# connector_v3.net
KiCad netlist of a schematic drawn in EAGLE
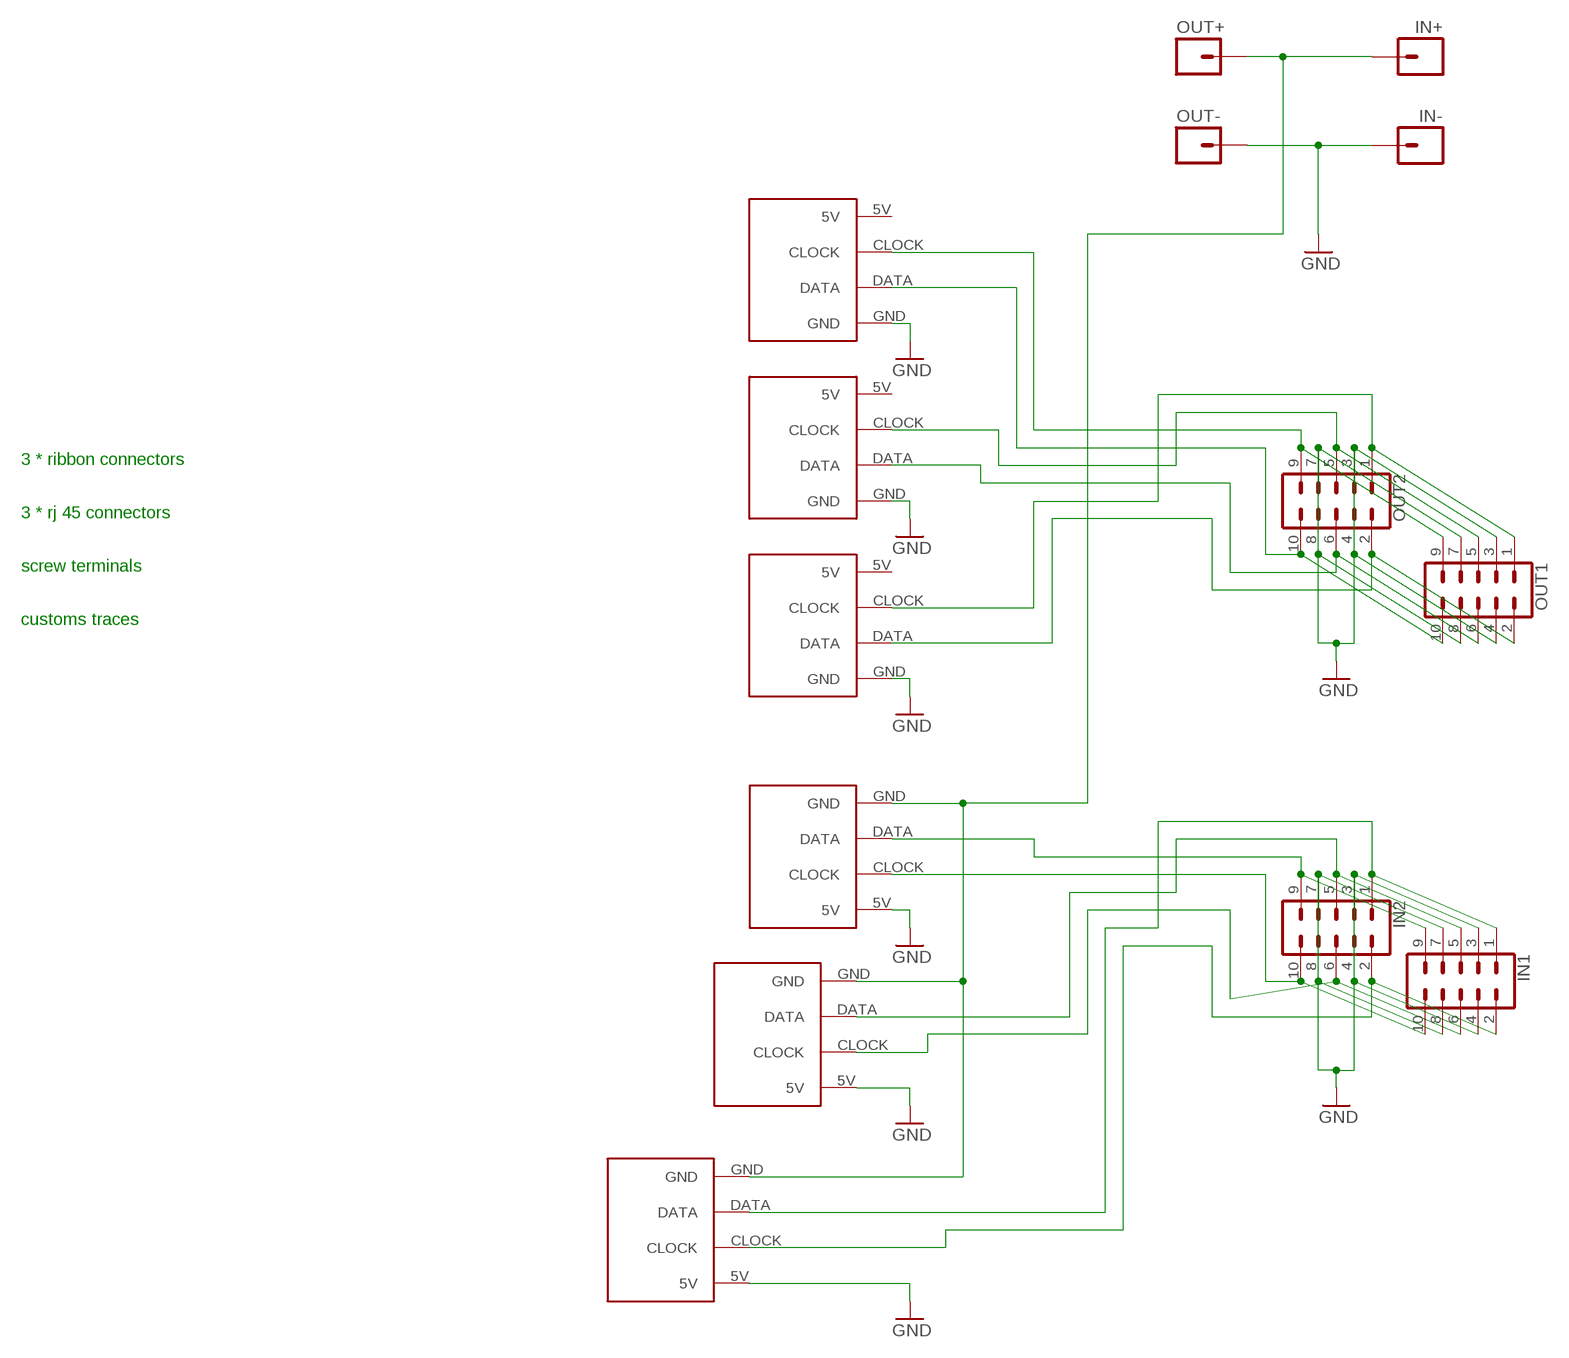
[diagram p0: schematic, sheet 1]

(export (version "E")
  (design (tool "Eeschema 10.0.6"))
  (components
    (comp (ref "IN+")
      (value "M01PTH_2MM")
      (footprint "eagle-import:1X01_2MM")
      (libsource (lib "eagle-import") (part "M01PTH_2MM"))
    )
    (comp (ref "IN-")
      (value "M01PTH_2MM")
      (footprint "eagle-import:1X01_2MM")
      (libsource (lib "eagle-import") (part "M01PTH_2MM"))
    )
    (comp (ref "IN1")
      (value "CONN_05X2SHD_LOCK")
      (footprint "eagle-import:2X5-SHROUDED_LOCK")
      (libsource (lib "eagle-import") (part "CONN_05X2SHD_LOCK"))
    )
    (comp (ref "IN2")
      (value "CONN_05X2SHD_LOCK")
      (footprint "eagle-import:2X5-SHROUDED_LOCK")
      (libsource (lib "eagle-import") (part "CONN_05X2SHD_LOCK"))
    )
    (comp (ref "INSTRIP1")
      (value "APA102STRIP")
      (footprint "eagle-import:APA102STRIP")
      (libsource (lib "eagle-import") (part "APA102STRIP"))
    )
    (comp (ref "INSTRIP2")
      (value "APA102STRIP")
      (footprint "eagle-import:APA102STRIP")
      (libsource (lib "eagle-import") (part "APA102STRIP"))
    )
    (comp (ref "INSTRIP3")
      (value "APA102STRIP")
      (footprint "eagle-import:APA102STRIP")
      (libsource (lib "eagle-import") (part "APA102STRIP"))
    )
    (comp (ref "OUT+")
      (value "M01PTH_2MM")
      (footprint "eagle-import:1X01_2MM")
      (libsource (lib "eagle-import") (part "M01PTH_2MM"))
    )
    (comp (ref "OUT-")
      (value "M01PTH_2MM")
      (footprint "eagle-import:1X01_2MM")
      (libsource (lib "eagle-import") (part "M01PTH_2MM"))
    )
    (comp (ref "OUT1")
      (value "CONN_05X2SHD_LOCK")
      (footprint "eagle-import:2X5-SHROUDED_LOCK")
      (libsource (lib "eagle-import") (part "CONN_05X2SHD_LOCK"))
    )
    (comp (ref "OUT2")
      (value "CONN_05X2SHD_LOCK")
      (footprint "eagle-import:2X5-SHROUDED_LOCK")
      (libsource (lib "eagle-import") (part "CONN_05X2SHD_LOCK"))
    )
    (comp (ref "OUTSTRIP1")
      (value "APA102STRIP")
      (footprint "eagle-import:APA102STRIP")
      (libsource (lib "eagle-import") (part "APA102STRIP"))
    )
    (comp (ref "OUTSTRIP2")
      (value "APA102STRIP")
      (footprint "eagle-import:APA102STRIP")
      (libsource (lib "eagle-import") (part "APA102STRIP"))
    )
    (comp (ref "OUTSTRIP3")
      (value "APA102STRIP")
      (footprint "eagle-import:APA102STRIP")
      (libsource (lib "eagle-import") (part "APA102STRIP"))
    )
  )
  (nets
    (net (code "1") (name "GND") (class "Default")
      (node (ref "IN-") (pin "1") (pinfunction "1_1") (pintype "passive"))
      (node (ref "IN1") (pin "3") (pinfunction "3_3") (pintype "passive"))
      (node (ref "IN1") (pin "4") (pinfunction "4_4") (pintype "passive"))
      (node (ref "IN1") (pin "7") (pinfunction "7_7") (pintype "passive"))
      (node (ref "IN1") (pin "8") (pinfunction "8_8") (pintype "passive"))
      (node (ref "IN2") (pin "3") (pinfunction "3_3") (pintype "passive"))
      (node (ref "IN2") (pin "4") (pinfunction "4_4") (pintype "passive"))
      (node (ref "IN2") (pin "7") (pinfunction "7_7") (pintype "passive"))
      (node (ref "IN2") (pin "8") (pinfunction "8_8") (pintype "passive"))
      (node (ref "INSTRIP1") (pin "5V") (pinfunction "5V_5V") (pintype "bidirectional"))
      (node (ref "INSTRIP2") (pin "5V") (pinfunction "5V_5V") (pintype "bidirectional"))
      (node (ref "INSTRIP3") (pin "5V") (pinfunction "5V_5V") (pintype "bidirectional"))
      (node (ref "OUT-") (pin "1") (pinfunction "1_1") (pintype "passive"))
      (node (ref "OUT1") (pin "3") (pinfunction "3_3") (pintype "passive"))
      (node (ref "OUT1") (pin "4") (pinfunction "4_4") (pintype "passive"))
      (node (ref "OUT1") (pin "7") (pinfunction "7_7") (pintype "passive"))
      (node (ref "OUT1") (pin "8") (pinfunction "8_8") (pintype "passive"))
      (node (ref "OUT2") (pin "3") (pinfunction "3_3") (pintype "passive"))
      (node (ref "OUT2") (pin "4") (pinfunction "4_4") (pintype "passive"))
      (node (ref "OUT2") (pin "7") (pinfunction "7_7") (pintype "passive"))
      (node (ref "OUT2") (pin "8") (pinfunction "8_8") (pintype "passive"))
      (node (ref "OUTSTRIP1") (pin "GND") (pinfunction "GND_GND") (pintype "bidirectional"))
      (node (ref "OUTSTRIP2") (pin "GND") (pinfunction "GND_GND") (pintype "bidirectional"))
      (node (ref "OUTSTRIP3") (pin "GND") (pinfunction "GND_GND") (pintype "bidirectional"))
    )
    (net (code "2") (name "Net-(IN+-Pad1)") (class "Default")
      (node (ref "IN+") (pin "1") (pinfunction "1_1") (pintype "passive"))
      (node (ref "INSTRIP1") (pin "GND") (pinfunction "GND_GND") (pintype "bidirectional"))
      (node (ref "INSTRIP2") (pin "GND") (pinfunction "GND_GND") (pintype "bidirectional"))
      (node (ref "INSTRIP3") (pin "GND") (pinfunction "GND_GND") (pintype "bidirectional"))
      (node (ref "OUT+") (pin "1") (pinfunction "1_1") (pintype "passive"))
    )
    (net (code "3") (name "Net-(IN1-Pad1)") (class "Default")
      (node (ref "IN1") (pin "1") (pinfunction "1_1") (pintype "passive"))
      (node (ref "IN2") (pin "1") (pinfunction "1_1") (pintype "passive"))
      (node (ref "INSTRIP1") (pin "DATA") (pinfunction "DATA_DATA") (pintype "bidirectional"))
    )
    (net (code "4") (name "Net-(IN1-Pad2)") (class "Default")
      (node (ref "IN1") (pin "2") (pinfunction "2_2") (pintype "passive"))
      (node (ref "IN2") (pin "2") (pinfunction "2_2") (pintype "passive"))
      (node (ref "INSTRIP1") (pin "CLOCK") (pinfunction "CLOCK_CLOCK") (pintype "bidirectional"))
    )
    (net (code "5") (name "Net-(IN1-Pad5)") (class "Default")
      (node (ref "IN1") (pin "5") (pinfunction "5_5") (pintype "passive"))
      (node (ref "IN2") (pin "5") (pinfunction "5_5") (pintype "passive"))
      (node (ref "INSTRIP2") (pin "DATA") (pinfunction "DATA_DATA") (pintype "bidirectional"))
    )
    (net (code "6") (name "Net-(IN1-Pad6)") (class "Default")
      (node (ref "IN1") (pin "6") (pinfunction "6_6") (pintype "passive"))
      (node (ref "IN2") (pin "6") (pinfunction "6_6") (pintype "passive"))
      (node (ref "INSTRIP2") (pin "CLOCK") (pinfunction "CLOCK_CLOCK") (pintype "bidirectional"))
    )
    (net (code "7") (name "Net-(IN1-Pad9)") (class "Default")
      (node (ref "IN1") (pin "9") (pinfunction "9_9") (pintype "passive"))
      (node (ref "IN2") (pin "9") (pinfunction "9_9") (pintype "passive"))
      (node (ref "INSTRIP3") (pin "DATA") (pinfunction "DATA_DATA") (pintype "bidirectional"))
    )
    (net (code "8") (name "Net-(IN1-Pad10)") (class "Default")
      (node (ref "IN1") (pin "10") (pinfunction "10_10") (pintype "passive"))
      (node (ref "IN2") (pin "10") (pinfunction "10_10") (pintype "passive"))
      (node (ref "INSTRIP3") (pin "CLOCK") (pinfunction "CLOCK_CLOCK") (pintype "bidirectional"))
    )
    (net (code "9") (name "Net-(OUT1-Pad1)") (class "Default")
      (node (ref "OUT1") (pin "1") (pinfunction "1_1") (pintype "passive"))
      (node (ref "OUT2") (pin "1") (pinfunction "1_1") (pintype "passive"))
      (node (ref "OUTSTRIP1") (pin "CLOCK") (pinfunction "CLOCK_CLOCK") (pintype "bidirectional"))
    )
    (net (code "10") (name "Net-(OUT1-Pad2)") (class "Default")
      (node (ref "OUT1") (pin "2") (pinfunction "2_2") (pintype "passive"))
      (node (ref "OUT2") (pin "2") (pinfunction "2_2") (pintype "passive"))
      (node (ref "OUTSTRIP1") (pin "DATA") (pinfunction "DATA_DATA") (pintype "bidirectional"))
    )
    (net (code "11") (name "Net-(OUT1-Pad5)") (class "Default")
      (node (ref "OUT1") (pin "5") (pinfunction "5_5") (pintype "passive"))
      (node (ref "OUT2") (pin "5") (pinfunction "5_5") (pintype "passive"))
      (node (ref "OUTSTRIP2") (pin "CLOCK") (pinfunction "CLOCK_CLOCK") (pintype "bidirectional"))
    )
    (net (code "12") (name "Net-(OUT1-Pad6)") (class "Default")
      (node (ref "OUT1") (pin "6") (pinfunction "6_6") (pintype "passive"))
      (node (ref "OUT2") (pin "6") (pinfunction "6_6") (pintype "passive"))
      (node (ref "OUTSTRIP2") (pin "DATA") (pinfunction "DATA_DATA") (pintype "bidirectional"))
    )
    (net (code "13") (name "Net-(OUT1-Pad9)") (class "Default")
      (node (ref "OUT1") (pin "9") (pinfunction "9_9") (pintype "passive"))
      (node (ref "OUT2") (pin "9") (pinfunction "9_9") (pintype "passive"))
      (node (ref "OUTSTRIP3") (pin "CLOCK") (pinfunction "CLOCK_CLOCK") (pintype "bidirectional"))
    )
    (net (code "14") (name "Net-(OUT1-Pad10)") (class "Default")
      (node (ref "OUT1") (pin "10") (pinfunction "10_10") (pintype "passive"))
      (node (ref "OUT2") (pin "10") (pinfunction "10_10") (pintype "passive"))
      (node (ref "OUTSTRIP3") (pin "DATA") (pinfunction "DATA_DATA") (pintype "bidirectional"))
    )
    (net (code "15") (name "unconnected-(OUTSTRIP1-Pad5V)") (class "Default")
      (node (ref "OUTSTRIP1") (pin "5V") (pinfunction "5V_5V") (pintype "bidirectional"))
    )
    (net (code "16") (name "unconnected-(OUTSTRIP2-Pad5V)") (class "Default")
      (node (ref "OUTSTRIP2") (pin "5V") (pinfunction "5V_5V") (pintype "bidirectional"))
    )
    (net (code "17") (name "unconnected-(OUTSTRIP3-Pad5V)") (class "Default")
      (node (ref "OUTSTRIP3") (pin "5V") (pinfunction "5V_5V") (pintype "bidirectional"))
    )
  )
)
